# Opam.net
KiCad netlist of a schematic drawn in Altium Designer
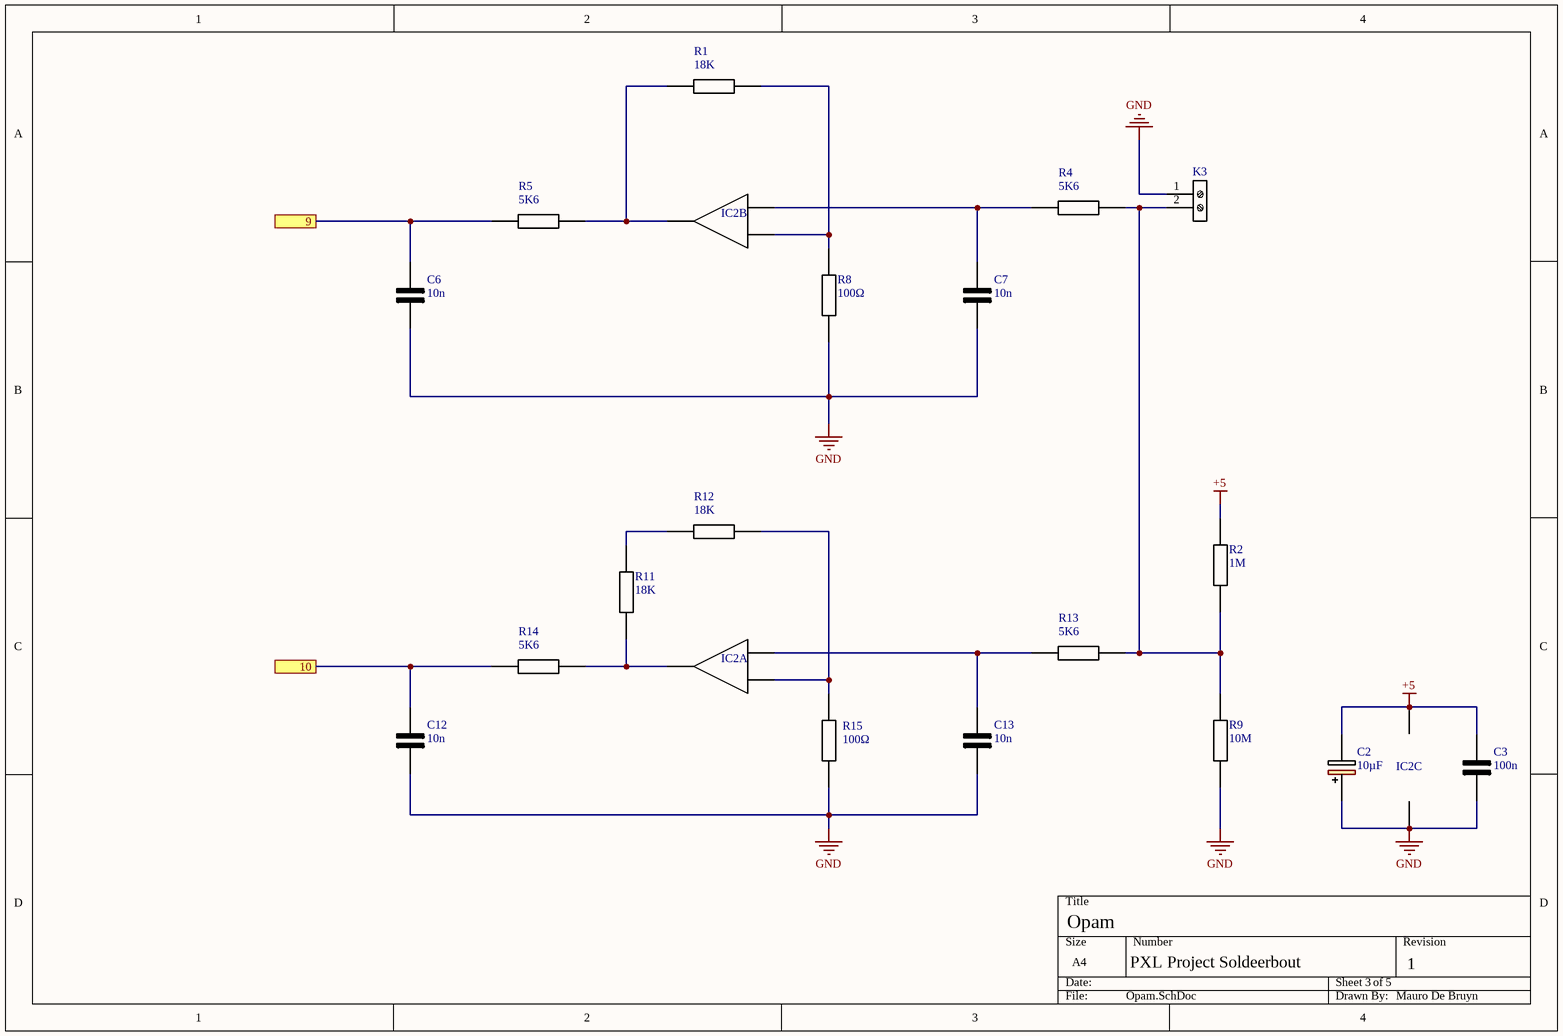
[diagram p0: Opam.SchDoc]

(export (version "E")
  (design (tool "Eeschema 10.0.6"))
  (components
    (comp (ref "C2")
      (value "10µF")
      (footprint "SamacSys:CAPPRD200W52D500H1250")
      (description "Capacitor Polarised")
      (fields
        (field (name "MOUSER2 PART NUMBER") "710-860020672010")
        (field (name "MANUFACTURER_PART_NUMBER") "860020672010")
      )
      (libsource (lib "SamacSys") (part "860020672010"))
    )
    (comp (ref "C3")
      (value "100n")
      (footprint "SamacSys:C0805")
      (description "Capacitor")
      (fields (field (name "MANUFACTURER_PART_NUMBER") "C0805C391G3GACTU"))
      (libsource (lib "SamacSys") (part "0805_1"))
    )
    (comp (ref "C6")
      (value "10n")
      (footprint "SamacSys:C0805")
      (description "Capacitor")
      (fields (field (name "MANUFACTURER_PART_NUMBER") "C0805C391G3GACTU"))
      (libsource (lib "SamacSys") (part "0805_1"))
    )
    (comp (ref "C7")
      (value "10n")
      (footprint "SamacSys:C0805")
      (description "Capacitor")
      (fields (field (name "MANUFACTURER_PART_NUMBER") "C0805C391G3GACTU"))
      (libsource (lib "SamacSys") (part "0805_1"))
    )
    (comp (ref "C12")
      (value "10n")
      (footprint "SamacSys:C0805")
      (description "Capacitor")
      (fields (field (name "MANUFACTURER_PART_NUMBER") "C0805C391G3GACTU"))
      (libsource (lib "SamacSys") (part "0805_1"))
    )
    (comp (ref "C13")
      (value "10n")
      (footprint "SamacSys:C0805")
      (description "Capacitor")
      (fields (field (name "MANUFACTURER_PART_NUMBER") "C0805C391G3GACTU"))
      (libsource (lib "SamacSys") (part "0805_1"))
    )
    (comp (ref "IC2")
      (value "MCP6002-E_P")
      (footprint "SamacSys:DIP781W56P254L950H533Q8N")
      (description "Integrated Circuit")
      (fields
        (field (name "MOUSER2 PART NUMBER") "579-MCP6002-E/P")
        (field (name "MANUFACTURER_PART_NUMBER") "MCP6002-E/P")
      )
      (libsource (lib "SamacSys") (part "MCP6002-E_P"))
    )
    (comp (ref "K3")
      (value "2 Pin Connector 1716020000")
      (footprint "SamacSys:1716020000")
      (description "Connector")
      (fields (field (name "MANUFACTURER_PART_NUMBER") "1716020000"))
      (libsource (lib "SamacSys") (part "2 Pin Connector 1716020000"))
    )
    (comp (ref "R1")
      (value "18K")
      (footprint "SamacSys:C0805")
      (description "Resistor")
      (fields (field (name "MANUFACTURER_PART_NUMBER") "C0805C391G3GACTU"))
      (libsource (lib "SamacSys") (part "0805"))
    )
    (comp (ref "R2")
      (value "1M")
      (footprint "SamacSys:C0805")
      (description "Resistor")
      (fields (field (name "MANUFACTURER_PART_NUMBER") "C0805C391G3GACTU"))
      (libsource (lib "SamacSys") (part "0805"))
    )
    (comp (ref "R4")
      (value "5K6")
      (footprint "SamacSys:C0805")
      (description "Resistor")
      (fields (field (name "MANUFACTURER_PART_NUMBER") "C0805C391G3GACTU"))
      (libsource (lib "SamacSys") (part "0805"))
    )
    (comp (ref "R5")
      (value "5K6")
      (footprint "SamacSys:C0805")
      (description "Resistor")
      (fields (field (name "MANUFACTURER_PART_NUMBER") "C0805C391G3GACTU"))
      (libsource (lib "SamacSys") (part "0805"))
    )
    (comp (ref "R8")
      (value "100Ω")
      (footprint "SamacSys:C0805")
      (description "Resistor")
      (fields (field (name "MANUFACTURER_PART_NUMBER") "C0805C391G3GACTU"))
      (libsource (lib "SamacSys") (part "0805"))
    )
    (comp (ref "R9")
      (value "10M")
      (footprint "SamacSys:C0805")
      (description "Resistor")
      (fields (field (name "MANUFACTURER_PART_NUMBER") "C0805C391G3GACTU"))
      (libsource (lib "SamacSys") (part "0805"))
    )
    (comp (ref "R11")
      (value "18K")
      (footprint "SamacSys:C0805")
      (description "Resistor")
      (fields (field (name "MANUFACTURER_PART_NUMBER") "C0805C391G3GACTU"))
      (libsource (lib "SamacSys") (part "0805"))
    )
    (comp (ref "R12")
      (value "18K")
      (footprint "SamacSys:C0805")
      (description "Resistor")
      (fields (field (name "MANUFACTURER_PART_NUMBER") "C0805C391G3GACTU"))
      (libsource (lib "SamacSys") (part "0805"))
    )
    (comp (ref "R13")
      (value "5K6")
      (footprint "SamacSys:C0805")
      (description "Resistor")
      (fields (field (name "MANUFACTURER_PART_NUMBER") "C0805C391G3GACTU"))
      (libsource (lib "SamacSys") (part "0805"))
    )
    (comp (ref "R14")
      (value "5K6")
      (footprint "SamacSys:C0805")
      (description "Resistor")
      (fields (field (name "MANUFACTURER_PART_NUMBER") "C0805C391G3GACTU"))
      (libsource (lib "SamacSys") (part "0805"))
    )
    (comp (ref "R15")
      (value "100Ω")
      (footprint "SamacSys:C0805")
      (description "Resistor")
      (fields (field (name "MANUFACTURER_PART_NUMBER") "C0805C391G3GACTU"))
      (libsource (lib "SamacSys") (part "0805"))
    )
  )
  (nets
    (net (code "1") (name "+5") (class "Default")
      (node (ref "C2") (pin "2") (pinfunction "-_2") (pintype "passive"))
      (node (ref "C3") (pin "2") (pinfunction "-_2") (pintype "passive"))
      (node (ref "IC2") (pin "8") (pinfunction "VDD_8") (pintype "passive"))
      (node (ref "R2") (pin "2") (pinfunction "2_2") (pintype "passive"))
    )
    (net (code "2") (name "/9") (class "Default")
      (node (ref "C6") (pin "2") (pinfunction "-_2") (pintype "passive"))
      (node (ref "R5") (pin "1") (pinfunction "1_1") (pintype "passive"))
    )
    (net (code "3") (name "/10") (class "Default")
      (node (ref "C12") (pin "2") (pinfunction "-_2") (pintype "passive"))
      (node (ref "R14") (pin "1") (pinfunction "1_1") (pintype "passive"))
    )
    (net (code "4") (name "GND") (class "Default")
      (node (ref "C12") (pin "1") (pinfunction "+_1") (pintype "passive"))
      (node (ref "C13") (pin "1") (pinfunction "+_1") (pintype "passive"))
      (node (ref "C2") (pin "1") (pinfunction "+_1") (pintype "passive"))
      (node (ref "C3") (pin "1") (pinfunction "+_1") (pintype "passive"))
      (node (ref "C6") (pin "1") (pinfunction "+_1") (pintype "passive"))
      (node (ref "C7") (pin "1") (pinfunction "+_1") (pintype "passive"))
      (node (ref "IC2") (pin "4") (pinfunction "VSS_4") (pintype "passive"))
      (node (ref "K3") (pin "1") (pinfunction "1_1") (pintype "passive"))
      (node (ref "R15") (pin "1") (pinfunction "1_1") (pintype "passive"))
      (node (ref "R8") (pin "1") (pinfunction "1_1") (pintype "passive"))
      (node (ref "R9") (pin "1") (pinfunction "1_1") (pintype "passive"))
    )
    (net (code "5") (name "Net-(C7--)") (class "Default")
      (node (ref "C7") (pin "2") (pinfunction "-_2") (pintype "passive"))
      (node (ref "IC2") (pin "5") (pinfunction "VINB+_5") (pintype "passive"))
      (node (ref "R4") (pin "1") (pinfunction "1_1") (pintype "passive"))
    )
    (net (code "6") (name "Net-(C13--)") (class "Default")
      (node (ref "C13") (pin "2") (pinfunction "-_2") (pintype "passive"))
      (node (ref "IC2") (pin "3") (pinfunction "VINA+_3") (pintype "passive"))
      (node (ref "R13") (pin "1") (pinfunction "1_1") (pintype "passive"))
    )
    (net (code "7") (name "Net-(IC2A-VINA-)") (class "Default")
      (node (ref "IC2") (pin "2") (pinfunction "VINA-_2") (pintype "passive"))
      (node (ref "R12") (pin "2") (pinfunction "2_2") (pintype "passive"))
      (node (ref "R15") (pin "2") (pinfunction "2_2") (pintype "passive"))
    )
    (net (code "8") (name "Net-(IC2A-VOUTA)") (class "Default")
      (node (ref "IC2") (pin "1") (pinfunction "VOUTA_1") (pintype "passive"))
      (node (ref "R11") (pin "1") (pinfunction "1_1") (pintype "passive"))
      (node (ref "R14") (pin "2") (pinfunction "2_2") (pintype "passive"))
    )
    (net (code "9") (name "Net-(IC2B-VINB-)") (class "Default")
      (node (ref "IC2") (pin "6") (pinfunction "VINB-_6") (pintype "passive"))
      (node (ref "R1") (pin "2") (pinfunction "2_2") (pintype "passive"))
      (node (ref "R8") (pin "2") (pinfunction "2_2") (pintype "passive"))
    )
    (net (code "10") (name "Net-(IC2B-VOUTB)") (class "Default")
      (node (ref "IC2") (pin "7") (pinfunction "VOUTB_7") (pintype "passive"))
      (node (ref "R1") (pin "1") (pinfunction "1_1") (pintype "passive"))
      (node (ref "R5") (pin "2") (pinfunction "2_2") (pintype "passive"))
    )
    (net (code "11") (name "Net-(K3-Pad2)") (class "Default")
      (node (ref "K3") (pin "2") (pinfunction "2_2") (pintype "passive"))
      (node (ref "R13") (pin "2") (pinfunction "2_2") (pintype "passive"))
      (node (ref "R2") (pin "1") (pinfunction "1_1") (pintype "passive"))
      (node (ref "R4") (pin "2") (pinfunction "2_2") (pintype "passive"))
      (node (ref "R9") (pin "2") (pinfunction "2_2") (pintype "passive"))
    )
    (net (code "12") (name "Net-(R11-Pad2)") (class "Default")
      (node (ref "R11") (pin "2") (pinfunction "2_2") (pintype "passive"))
      (node (ref "R12") (pin "1") (pinfunction "1_1") (pintype "passive"))
    )
  )
)
